# Sensor_Recalibration_Circuit.net
KiCad netlist of a schematic drawn in Altium Designer
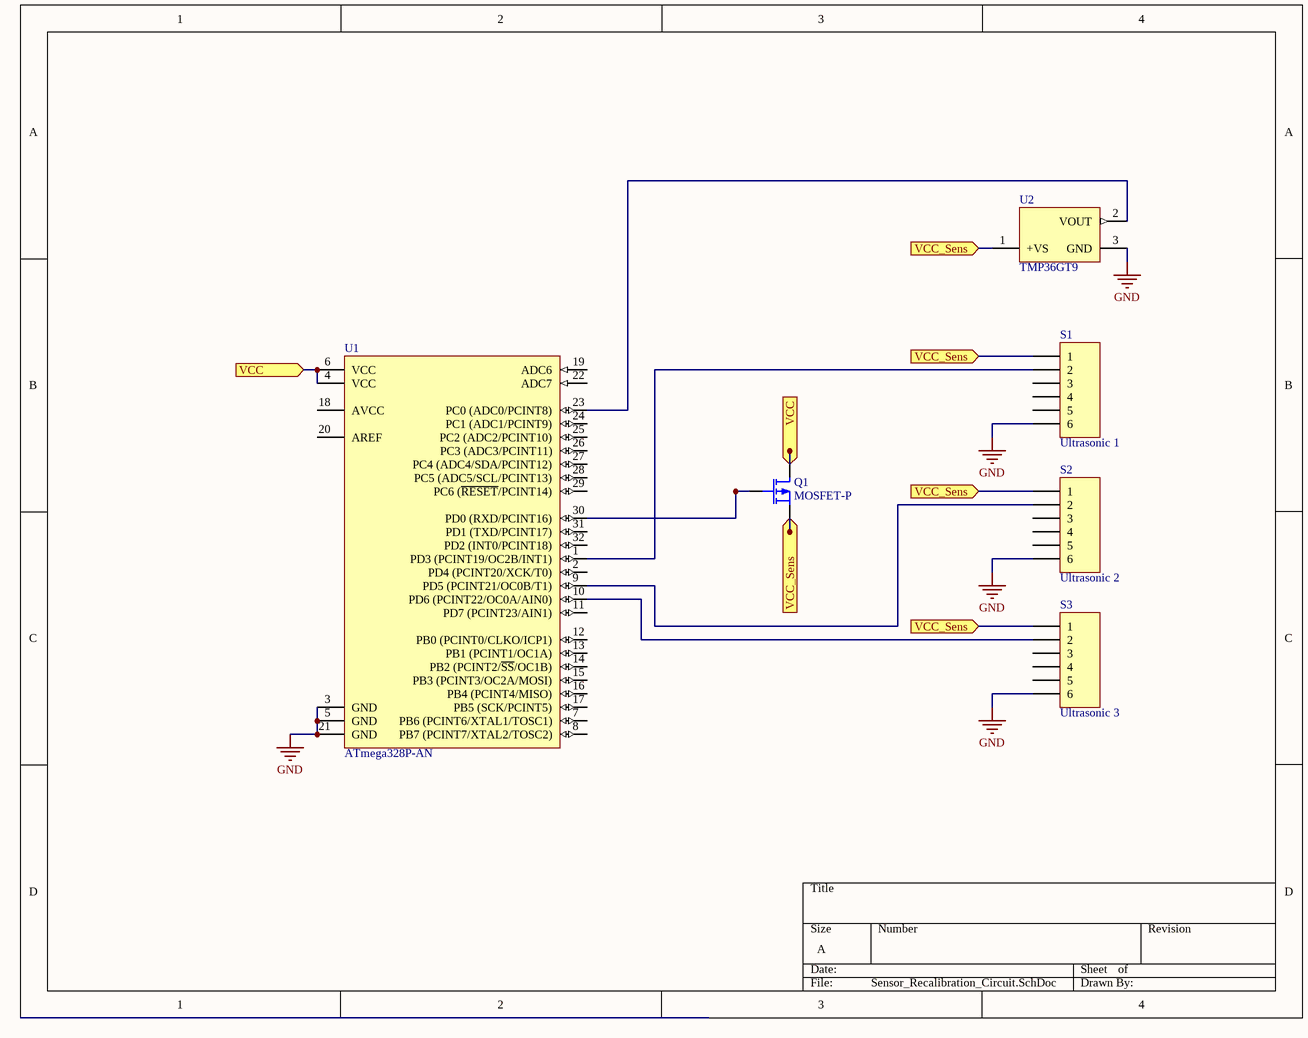
[diagram p0: Sensor_Recalibration_Circuit.SchDoc]

(export (version "E")
  (design (tool "Eeschema 10.0.6"))
  (components
    (comp (ref "Q1")
      (value "MOSFET-P")
      (footprint "E3")
      (description "P-Channel MOSFET")
      (fields (field (name "PUBLISHER") "Altium Limited"))
      (libsource (lib "Miscellaneous Devices") (part "MOSFET-P"))
    )
    (comp (ref "S1")
      (value "Ultrasonic 1")
      (footprint "HDR1X6")
      (description "Header, 6-Pin")
      (fields (field (name "PUBLISHER") "Altium Limited"))
      (libsource (lib "Miscellaneous Connectors") (part "Header 6"))
    )
    (comp (ref "S2")
      (value "Ultrasonic 2")
      (footprint "HDR1X6")
      (description "Header, 6-Pin")
      (fields (field (name "PUBLISHER") "Altium Limited"))
      (libsource (lib "Miscellaneous Connectors") (part "Header 6"))
    )
    (comp (ref "S3")
      (value "Ultrasonic 3")
      (footprint "HDR1X6")
      (description "Header, 6-Pin")
      (fields (field (name "PUBLISHER") "Altium Limited"))
      (libsource (lib "Miscellaneous Connectors") (part "Header 6"))
    )
    (comp (ref "U1")
      (value "ATmega328P-AN")
      (footprint "32A_N")
      (libsource (lib "Atmel Microcontroller megaAVR") (part "ATmega328P-AN"))
    )
    (comp (ref "U2")
      (value "TMP36GT9")
      (footprint "ADI-T-3")
      (description "Low Voltage Temperature Sensor, 2.7 to 5.5 V Supply, Industrial, 3-pin TO92 (T-3), Tray")
      (fields (field (name "MANUFACTURER") "Analog Devices"))
      (libsource (lib "Analog Devices Temperature Sensors") (part "TMP36GT9"))
    )
  )
  (nets
    (net (code "1") (name "/VCC") (class "Default")
      (node (ref "Q1") (pin "1") (pinfunction "D_1") (pintype "passive"))
      (node (ref "U1") (pin "4") (pinfunction "VCC_4") (pintype "power_in"))
      (node (ref "U1") (pin "6") (pinfunction "VCC_6") (pintype "power_in"))
    )
    (net (code "2") (name "/VCC_Sens") (class "Default")
      (node (ref "Q1") (pin "3") (pinfunction "S_3") (pintype "passive"))
      (node (ref "S1") (pin "1") (pinfunction "1_1") (pintype "passive"))
      (node (ref "S2") (pin "1") (pinfunction "1_1") (pintype "passive"))
      (node (ref "S3") (pin "1") (pinfunction "1_1") (pintype "passive"))
      (node (ref "U2") (pin "1") (pinfunction "+VS_1") (pintype "power_in"))
    )
    (net (code "3") (name "GND") (class "Default")
      (node (ref "S1") (pin "6") (pinfunction "6_6") (pintype "passive"))
      (node (ref "S2") (pin "6") (pinfunction "6_6") (pintype "passive"))
      (node (ref "S3") (pin "6") (pinfunction "6_6") (pintype "passive"))
      (node (ref "U1") (pin "21") (pinfunction "GND_21") (pintype "power_in"))
      (node (ref "U1") (pin "3") (pinfunction "GND_3") (pintype "power_in"))
      (node (ref "U1") (pin "5") (pinfunction "GND_5") (pintype "power_in"))
      (node (ref "U2") (pin "3") (pinfunction "GND_3") (pintype "power_in"))
    )
    (net (code "4") (name "Net-(Q1-G)") (class "Default")
      (node (ref "Q1") (pin "2") (pinfunction "G_2") (pintype "passive"))
      (node (ref "U1") (pin "30") (pinfunction "PD0_(RXD/PCINT16)_30") (pintype "bidirectional"))
    )
    (net (code "5") (name "Net-(U1-PC0_(ADC0{slash}PCINT8))") (class "Default")
      (node (ref "U1") (pin "23") (pinfunction "PC0_(ADC0/PCINT8)_23") (pintype "bidirectional"))
      (node (ref "U2") (pin "2") (pinfunction "VOUT_2") (pintype "output"))
    )
    (net (code "6") (name "Net-(U1-PD3_(PCINT19{slash}OC2B{slash}INT1))") (class "Default")
      (node (ref "S1") (pin "2") (pinfunction "2_2") (pintype "passive"))
      (node (ref "U1") (pin "1") (pinfunction "PD3_(PCINT19/OC2B/INT1)_1") (pintype "bidirectional"))
    )
    (net (code "7") (name "Net-(U1-PD5_(PCINT21{slash}OC0B{slash}T1))") (class "Default")
      (node (ref "S2") (pin "2") (pinfunction "2_2") (pintype "passive"))
      (node (ref "U1") (pin "9") (pinfunction "PD5_(PCINT21/OC0B/T1)_9") (pintype "bidirectional"))
    )
    (net (code "8") (name "Net-(U1-PD6_(PCINT22{slash}OC0A{slash}AIN0))") (class "Default")
      (node (ref "S3") (pin "2") (pinfunction "2_2") (pintype "passive"))
      (node (ref "U1") (pin "10") (pinfunction "PD6_(PCINT22/OC0A/AIN0)_10") (pintype "bidirectional"))
    )
    (net (code "9") (name "unconnected-(S1-Pad3)") (class "Default")
      (node (ref "S1") (pin "3") (pinfunction "3_3") (pintype "passive"))
    )
    (net (code "10") (name "unconnected-(S1-Pad4)") (class "Default")
      (node (ref "S1") (pin "4") (pinfunction "4_4") (pintype "passive"))
    )
    (net (code "11") (name "unconnected-(S1-Pad5)") (class "Default")
      (node (ref "S1") (pin "5") (pinfunction "5_5") (pintype "passive"))
    )
    (net (code "12") (name "unconnected-(S2-Pad3)") (class "Default")
      (node (ref "S2") (pin "3") (pinfunction "3_3") (pintype "passive"))
    )
    (net (code "13") (name "unconnected-(S2-Pad4)") (class "Default")
      (node (ref "S2") (pin "4") (pinfunction "4_4") (pintype "passive"))
    )
    (net (code "14") (name "unconnected-(S2-Pad5)") (class "Default")
      (node (ref "S2") (pin "5") (pinfunction "5_5") (pintype "passive"))
    )
    (net (code "15") (name "unconnected-(S3-Pad3)") (class "Default")
      (node (ref "S3") (pin "3") (pinfunction "3_3") (pintype "passive"))
    )
    (net (code "16") (name "unconnected-(S3-Pad4)") (class "Default")
      (node (ref "S3") (pin "4") (pinfunction "4_4") (pintype "passive"))
    )
    (net (code "17") (name "unconnected-(S3-Pad5)") (class "Default")
      (node (ref "S3") (pin "5") (pinfunction "5_5") (pintype "passive"))
    )
    (net (code "18") (name "unconnected-(U1-ADC6-Pad19)") (class "Default")
      (node (ref "U1") (pin "19") (pinfunction "ADC6_19") (pintype "input"))
    )
    (net (code "19") (name "unconnected-(U1-ADC7-Pad22)") (class "Default")
      (node (ref "U1") (pin "22") (pinfunction "ADC7_22") (pintype "input"))
    )
    (net (code "20") (name "unconnected-(U1-AREF-Pad20)") (class "Default")
      (node (ref "U1") (pin "20") (pinfunction "AREF_20") (pintype "passive"))
    )
    (net (code "21") (name "unconnected-(U1-AVCC-Pad18)") (class "Default")
      (node (ref "U1") (pin "18") (pinfunction "AVCC_18") (pintype "power_in"))
    )
    (net (code "22") (name "unconnected-(U1-PB0_(PCINT0{slash}CLKO{slash}ICP1)-Pad12)") (class "Default")
      (node (ref "U1") (pin "12") (pinfunction "PB0_(PCINT0/CLKO/ICP1)_12") (pintype "bidirectional"))
    )
    (net (code "23") (name "unconnected-(U1-PB1_(PCINT1{slash}OC1A)-Pad13)") (class "Default")
      (node (ref "U1") (pin "13") (pinfunction "PB1_(PCINT1/OC1A)_13") (pintype "bidirectional"))
    )
    (net (code "24") (name "unconnected-(U1-PB2_(PCINT2{slash}~{SS}{slash}OC1B)-Pad14)") (class "Default")
      (node (ref "U1") (pin "14") (pinfunction "PB2_(PCINT2/~{SS}/OC1B)_14") (pintype "bidirectional"))
    )
    (net (code "25") (name "unconnected-(U1-PB3_(PCINT3{slash}OC2A{slash}MOSI)-Pad15)") (class "Default")
      (node (ref "U1") (pin "15") (pinfunction "PB3_(PCINT3/OC2A/MOSI)_15") (pintype "bidirectional"))
    )
    (net (code "26") (name "unconnected-(U1-PB4_(PCINT4{slash}MISO)-Pad16)") (class "Default")
      (node (ref "U1") (pin "16") (pinfunction "PB4_(PCINT4/MISO)_16") (pintype "bidirectional"))
    )
    (net (code "27") (name "unconnected-(U1-PB5_(SCK{slash}PCINT5)-Pad17)") (class "Default")
      (node (ref "U1") (pin "17") (pinfunction "PB5_(SCK/PCINT5)_17") (pintype "bidirectional"))
    )
    (net (code "28") (name "unconnected-(U1-PB6_(PCINT6{slash}XTAL1{slash}TOSC1)-Pad7)") (class "Default")
      (node (ref "U1") (pin "7") (pinfunction "PB6_(PCINT6/XTAL1/TOSC1)_7") (pintype "bidirectional"))
    )
    (net (code "29") (name "unconnected-(U1-PB7_(PCINT7{slash}XTAL2{slash}TOSC2)-Pad8)") (class "Default")
      (node (ref "U1") (pin "8") (pinfunction "PB7_(PCINT7/XTAL2/TOSC2)_8") (pintype "bidirectional"))
    )
    (net (code "30") (name "unconnected-(U1-PC1_(ADC1{slash}PCINT9)-Pad24)") (class "Default")
      (node (ref "U1") (pin "24") (pinfunction "PC1_(ADC1/PCINT9)_24") (pintype "bidirectional"))
    )
    (net (code "31") (name "unconnected-(U1-PC2_(ADC2{slash}PCINT10)-Pad25)") (class "Default")
      (node (ref "U1") (pin "25") (pinfunction "PC2_(ADC2/PCINT10)_25") (pintype "bidirectional"))
    )
    (net (code "32") (name "unconnected-(U1-PC3_(ADC3{slash}PCINT11)-Pad26)") (class "Default")
      (node (ref "U1") (pin "26") (pinfunction "PC3_(ADC3/PCINT11)_26") (pintype "bidirectional"))
    )
    (net (code "33") (name "unconnected-(U1-PC4_(ADC4{slash}SDA{slash}PCINT12)-Pad27)") (class "Default")
      (node (ref "U1") (pin "27") (pinfunction "PC4_(ADC4/SDA/PCINT12)_27") (pintype "bidirectional"))
    )
    (net (code "34") (name "unconnected-(U1-PC5_(ADC5{slash}SCL{slash}PCINT13)-Pad28)") (class "Default")
      (node (ref "U1") (pin "28") (pinfunction "PC5_(ADC5/SCL/PCINT13)_28") (pintype "bidirectional"))
    )
    (net (code "35") (name "unconnected-(U1-PC6_(~{RESET}{slash}PCINT14)-Pad29)") (class "Default")
      (node (ref "U1") (pin "29") (pinfunction "PC6_(~{RESET}/PCINT14)_29") (pintype "bidirectional"))
    )
    (net (code "36") (name "unconnected-(U1-PD1_(TXD{slash}PCINT17)-Pad31)") (class "Default")
      (node (ref "U1") (pin "31") (pinfunction "PD1_(TXD/PCINT17)_31") (pintype "bidirectional"))
    )
    (net (code "37") (name "unconnected-(U1-PD2_(INT0{slash}PCINT18)-Pad32)") (class "Default")
      (node (ref "U1") (pin "32") (pinfunction "PD2_(INT0/PCINT18)_32") (pintype "bidirectional"))
    )
    (net (code "38") (name "unconnected-(U1-PD4_(PCINT20{slash}XCK{slash}T0)-Pad2)") (class "Default")
      (node (ref "U1") (pin "2") (pinfunction "PD4_(PCINT20/XCK/T0)_2") (pintype "bidirectional"))
    )
    (net (code "39") (name "unconnected-(U1-PD7_(PCINT23{slash}AIN1)-Pad11)") (class "Default")
      (node (ref "U1") (pin "11") (pinfunction "PD7_(PCINT23/AIN1)_11") (pintype "bidirectional"))
    )
  )
)
